# FingerPrint.net
KiCad netlist of a schematic drawn in Altium Designer
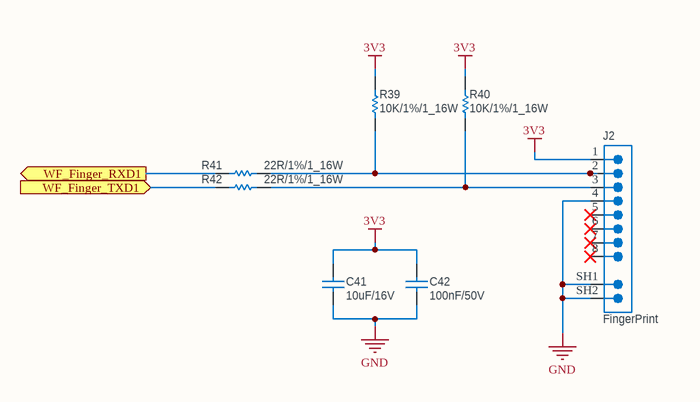
[diagram p0: FingerPrint.SchDoc]

(export (version "E")
  (design (tool "Eeschema 10.0.6"))
  (components
    (comp (ref "C41")
      (value "10uF/16V")
      (footprint "CAP_0603")
      (description "CAP, size 0603, 10uF, 16V")
      (fields (field (name "SUPPLY PART NUMBER") "Tụ Gốm 0603 10uF 16V"))
      (libsource (lib "BluetoothTracking") (part "Ceramic_Cap_10uF_16V_0603"))
    )
    (comp (ref "C42")
      (value "100nF/50V")
      (footprint "CAP_0603")
      (description "CAP, size 0603, 100nF, 50V")
      (fields (field (name "SUPPLY PART NUMBER") "Tụ Gốm 0603 100nF (0.1uF) 50V"))
      (libsource (lib "BluetoothTracking") (part "Ceramic_Cap_100nF_50V_0603"))
    )
    (comp (ref "J2")
      (value "FingerPrint")
      (footprint "MX_1.25mm_8P")
      (description "Đầu MX1.25mm 8 Chân Dán SMD Thẳng Đứng")
      (libsource (lib "BluetoothTracking") (part "MX_1.25mm_8P"))
    )
    (comp (ref "R39")
      (value "10K/1%/1_16W")
      (footprint "RESISTOR_0402")
      (description "Resistor 0402 10KOhm 1% 1_16W")
      (fields (field (name "SUPPLY PART NUMBER") "Điện Trở 10 KOhm 0402 1%"))
      (libsource (lib "BluetoothTracking") (part "Res_10K_0402_1%"))
    )
    (comp (ref "R40")
      (value "10K/1%/1_16W")
      (footprint "RESISTOR_0402")
      (description "Resistor 0402 10KOhm 1% 1_16W")
      (fields (field (name "SUPPLY PART NUMBER") "Điện Trở 10 KOhm 0402 1%"))
      (libsource (lib "BluetoothTracking") (part "Res_10K_0402_1%"))
    )
    (comp (ref "R41")
      (value "22R/1%/1_16W")
      (footprint "RESISTOR_0402")
      (description "Resistor 0402 22 Ohm 1% 1_16W")
      (libsource (lib "BluetoothTracking") (part "Res_22R_0402_1%"))
    )
    (comp (ref "R42")
      (value "22R/1%/1_16W")
      (footprint "RESISTOR_0402")
      (description "Resistor 0402 22 Ohm 1% 1_16W")
      (libsource (lib "BluetoothTracking") (part "Res_22R_0402_1%"))
    )
  )
  (nets
    (net (code "1") (name "/WF_Finger_RXD1") (class "Default")
      (node (ref "R41") (pin "1") (pinfunction "1_1") (pintype "passive"))
    )
    (net (code "2") (name "/WF_Finger_TXD1") (class "Default")
      (node (ref "R42") (pin "1") (pinfunction "1_1") (pintype "passive"))
    )
    (net (code "3") (name "3V3") (class "Default")
      (node (ref "C41") (pin "2") (pinfunction "2_2") (pintype "passive"))
      (node (ref "C42") (pin "2") (pinfunction "2_2") (pintype "passive"))
      (node (ref "J2") (pin "1") (pinfunction "1_1") (pintype "passive"))
      (node (ref "R39") (pin "2") (pinfunction "2_2") (pintype "passive"))
      (node (ref "R40") (pin "2") (pinfunction "2_2") (pintype "passive"))
    )
    (net (code "4") (name "GND") (class "Default")
      (node (ref "C41") (pin "1") (pinfunction "1_1") (pintype "passive"))
      (node (ref "C42") (pin "1") (pinfunction "1_1") (pintype "passive"))
      (node (ref "J2") (pin "4") (pinfunction "4_4") (pintype "passive"))
      (node (ref "J2") (pin "SH1") (pinfunction "SHIELD_SH1") (pintype "passive"))
      (node (ref "J2") (pin "SH2") (pinfunction "SHIELD_SH2") (pintype "passive"))
    )
    (net (code "5") (name "Net-(J2-Pad2)") (class "Default")
      (node (ref "J2") (pin "2") (pinfunction "2_2") (pintype "passive"))
      (node (ref "R39") (pin "1") (pinfunction "1_1") (pintype "passive"))
      (node (ref "R41") (pin "2") (pinfunction "2_2") (pintype "passive"))
    )
    (net (code "6") (name "Net-(J2-Pad3)") (class "Default")
      (node (ref "J2") (pin "3") (pinfunction "3_3") (pintype "passive"))
      (node (ref "R40") (pin "1") (pinfunction "1_1") (pintype "passive"))
      (node (ref "R42") (pin "2") (pinfunction "2_2") (pintype "passive"))
    )
    (net (code "7") (name "unconnected-(J2-Pad5)") (class "Default")
      (node (ref "J2") (pin "5") (pinfunction "5_5") (pintype "passive+no_connect"))
    )
    (net (code "8") (name "unconnected-(J2-Pad6)") (class "Default")
      (node (ref "J2") (pin "6") (pinfunction "6_6") (pintype "passive+no_connect"))
    )
    (net (code "9") (name "unconnected-(J2-Pad7)") (class "Default")
      (node (ref "J2") (pin "7") (pinfunction "7_7") (pintype "passive+no_connect"))
    )
    (net (code "10") (name "unconnected-(J2-Pad8)") (class "Default")
      (node (ref "J2") (pin "8") (pinfunction "8_8") (pintype "passive+no_connect"))
    )
  )
)
